# Sheet.net
KiCad netlist of a schematic drawn in Altium Designer
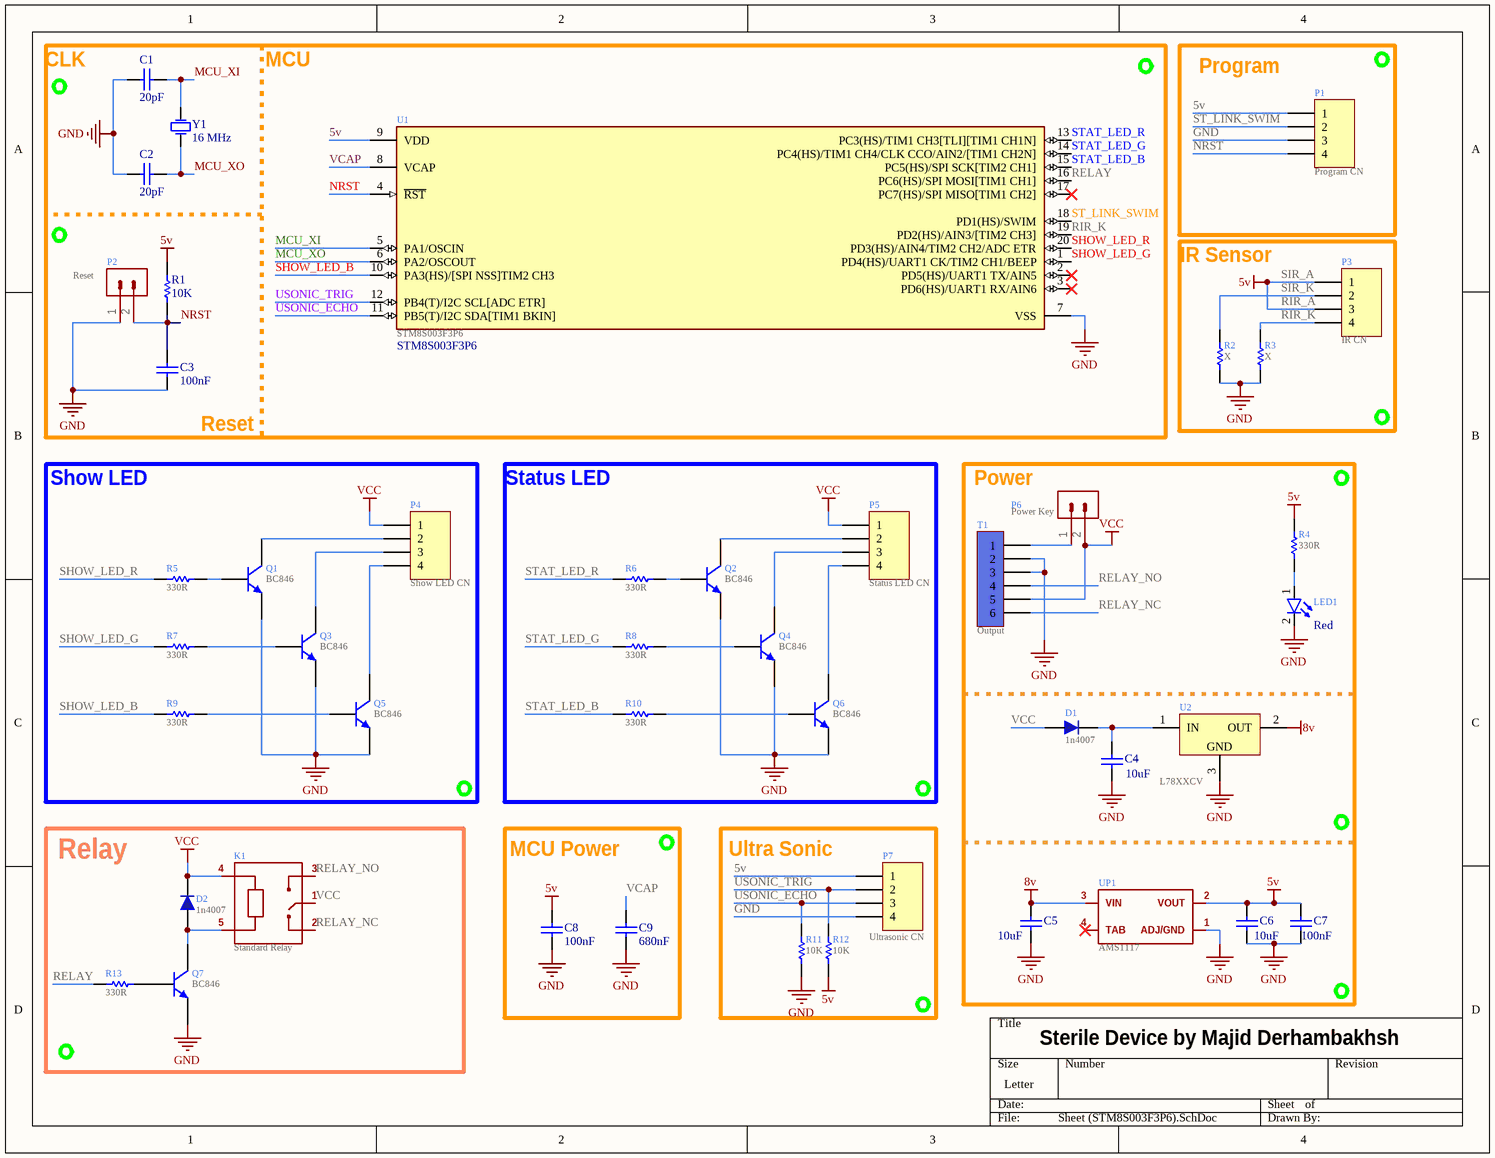
[diagram p0: Sheet (STM8S003F3P6).SchDoc]

(export (version "E")
  (design (tool "Eeschema 10.0.6"))
  (components
    (comp (ref "C1")
      (value "20pF")
      (footprint "CAP805")
      (description "TOTAL CAPACITOR SMD PACK")
      (fields (field (name "DESIGNER") "Majid Derhambakhsh"))
      (libsource (lib "Altium") (part "CAP SMD PACKAGE"))
    )
    (comp (ref "C2")
      (value "20pF")
      (footprint "CAP805")
      (description "TOTAL CAPACITOR SMD PACK")
      (fields (field (name "DESIGNER") "Majid Derhambakhsh"))
      (libsource (lib "Altium") (part "CAP SMD PACKAGE"))
    )
    (comp (ref "C3")
      (value "100nF")
      (footprint "Cap1206_(3216X15L)")
      (description "TOTAL CAPACITOR SMD PACK")
      (fields (field (name "DESIGNER") "Majid Derhambakhsh"))
      (libsource (lib "Altium") (part "CAP SMD PACKAGE"))
    )
    (comp (ref "C4")
      (value "10uF")
      (footprint "Cap1206_(3216X15)")
      (description "TOTAL CAPACITOR SMD PACK")
      (fields (field (name "DESIGNER") "Abbas Basereh"))
      (libsource (lib "Altium") (part "CAP SMD PACKAGE"))
    )
    (comp (ref "C5")
      (value "10uF")
      (footprint "Cap1206_(3216X15)")
      (description "TOTAL CAPACITOR SMD PACK")
      (fields (field (name "DESIGNER") "Abbas Basereh"))
      (libsource (lib "Altium") (part "CAP SMD PACKAGE"))
    )
    (comp (ref "C6")
      (value "10uF")
      (footprint "Cap1206_(3216X15)")
      (description "TOTAL CAPACITOR SMD PACK")
      (fields (field (name "DESIGNER") "Abbas Basereh"))
      (libsource (lib "Altium") (part "CAP SMD PACKAGE"))
    )
    (comp (ref "C7")
      (value "100nF")
      (footprint "Cap1206_(3216X15)")
      (description "TOTAL CAPACITOR SMD PACK")
      (fields (field (name "DESIGNER") "Majid Derhambakhsh"))
      (libsource (lib "Altium") (part "CAP SMD PACKAGE"))
    )
    (comp (ref "C8")
      (value "100nF")
      (footprint "Cap1206_(3216X15L)")
      (description "TOTAL CAPACITOR SMD PACK")
      (fields (field (name "DESIGNER") "Majid Derhambakhsh"))
      (libsource (lib "Altium") (part "CAP SMD PACKAGE"))
    )
    (comp (ref "C9")
      (value "680nF")
      (footprint "Cap1206_(3216X15L)")
      (description "TOTAL CAPACITOR SMD PACK")
      (fields (field (name "DESIGNER") "Majid Derhambakhsh"))
      (libsource (lib "Altium") (part "CAP SMD PACKAGE"))
    )
    (comp (ref "D1")
      (value "1n4007")
      (footprint "DIOM4629X24N")
      (description "Standard Rectifiers")
      (fields (field (name "MANUFACTURER") "DC COMPONENTS") (field (name "DESIGNER") "Abbas Basereh"))
      (libsource (lib "Altium") (part "1n4007 SMD M7"))
    )
    (comp (ref "D2")
      (value "1n4007")
      (footprint "DIOM4629X24N")
      (description "Standard Rectifiers")
      (fields (field (name "MANUFACTURER") "DC COMPONENTS") (field (name "DESIGNER") "Abbas Basereh"))
      (libsource (lib "Altium") (part "1n4007 SMD M7"))
    )
    (comp (ref "K1")
      (value "Standard Relay")
      (footprint "Milon Relay (18.85x15.35x15.70)")
      (description "Relay SPDT POWER NEEDLE")
      (fields (field (name "DESIGNER") "Ali Hafizi"))
      (libsource (lib "Altium library") (part "Relay"))
    )
    (comp (ref "LED1")
      (value "Red")
      (footprint "LED SMD 1206")
      (fields (field (name "COLOR") "Red") (field (name "DESIGNER") "Saeid Jorablo"))
      (libsource (lib "My Library") (part "LED"))
    )
    (comp (ref "P1")
      (value "Program CN")
      (footprint "HDR1X4")
      (description "Header, 4-Pin")
      (fields (field (name "PUBLISHER") "Altium Limited"))
      (libsource (lib "Miscellaneous Connectors") (part "Header 4"))
    )
    (comp (ref "P2")
      (value "Reset")
      (footprint "HDR 1X2 DIP TOP")
      (description "Header, 2-Pin")
      (fields (field (name "PUBLISHER") "Altium Limited"))
      (libsource (lib "Altium library") (part "Header 2"))
    )
    (comp (ref "P3")
      (value "IR CN")
      (footprint "HDR1X4")
      (description "Header, 4-Pin")
      (fields (field (name "PUBLISHER") "Altium Limited"))
      (libsource (lib "Miscellaneous Connectors") (part "Header 4"))
    )
    (comp (ref "P4")
      (value "Show LED CN")
      (footprint "HDR1X4")
      (description "Header, 4-Pin")
      (fields (field (name "PUBLISHER") "Altium Limited"))
      (libsource (lib "Miscellaneous Connectors") (part "Header 4"))
    )
    (comp (ref "P5")
      (value "Status LED CN")
      (footprint "HDR1X4")
      (description "Header, 4-Pin")
      (fields (field (name "PUBLISHER") "Altium Limited"))
      (libsource (lib "Miscellaneous Connectors") (part "Header 4"))
    )
    (comp (ref "P6")
      (value "Power Key")
      (footprint "HDR 1X2 DIP TOP")
      (description "Header, 2-Pin")
      (fields (field (name "PUBLISHER") "Altium Limited"))
      (libsource (lib "Altium library") (part "Header 2"))
    )
    (comp (ref "P7")
      (value "Ultrasonic CN")
      (footprint "HDR1X4")
      (description "Header, 4-Pin")
      (fields (field (name "PUBLISHER") "Altium Limited"))
      (libsource (lib "Miscellaneous Connectors") (part "Header 4"))
    )
    (comp (ref "Q1")
      (value "BC846")
      (footprint "SOT23_L")
      (description "NPN General-purpose Transistor")
      (fields (field (name "PUBLISHER") "Abbas Basereh"))
      (libsource (lib "Altium") (part "BC846"))
    )
    (comp (ref "Q2")
      (value "BC846")
      (footprint "SOT23_L")
      (description "NPN General-purpose Transistor")
      (fields (field (name "PUBLISHER") "Abbas Basereh"))
      (libsource (lib "Altium") (part "BC846"))
    )
    (comp (ref "Q3")
      (value "BC846")
      (footprint "SOT23_L")
      (description "NPN General-purpose Transistor")
      (fields (field (name "PUBLISHER") "Abbas Basereh"))
      (libsource (lib "Altium") (part "BC846"))
    )
    (comp (ref "Q4")
      (value "BC846")
      (footprint "SOT23_L")
      (description "NPN General-purpose Transistor")
      (fields (field (name "PUBLISHER") "Abbas Basereh"))
      (libsource (lib "Altium") (part "BC846"))
    )
    (comp (ref "Q5")
      (value "BC846")
      (footprint "SOT23_L")
      (description "NPN General-purpose Transistor")
      (fields (field (name "PUBLISHER") "Abbas Basereh"))
      (libsource (lib "Altium") (part "BC846"))
    )
    (comp (ref "Q6")
      (value "BC846")
      (footprint "SOT23_L")
      (description "NPN General-purpose Transistor")
      (fields (field (name "PUBLISHER") "Abbas Basereh"))
      (libsource (lib "Altium") (part "BC846"))
    )
    (comp (ref "Q7")
      (value "BC846")
      (footprint "SOT23_L")
      (description "NPN General-purpose Transistor")
      (fields (field (name "PUBLISHER") "Abbas Basereh"))
      (libsource (lib "Altium") (part "BC846"))
    )
    (comp (ref "R1")
      (value "10K")
      (footprint "RES1206 _(3216X08L)")
      (description "TOTAL SMD RESISTOR PACK")
      (fields (field (name "DESIGNER") "Abbas Basereh"))
      (libsource (lib "Altium") (part "RES SMD PACKAGE"))
    )
    (comp (ref "R2")
      (value "X")
      (footprint "RES1206 _(3216X08L)")
      (description "TOTAL SMD RESISTOR PACK")
      (fields (field (name "DESIGNER") "Abbas Basereh"))
      (libsource (lib "Altium") (part "RES SMD PACKAGE"))
    )
    (comp (ref "R3")
      (value "X")
      (footprint "RES1206 _(3216X08L)")
      (description "TOTAL SMD RESISTOR PACK")
      (fields (field (name "DESIGNER") "Abbas Basereh"))
      (libsource (lib "Altium") (part "RES SMD PACKAGE"))
    )
    (comp (ref "R4")
      (value "330R")
      (footprint "RES1206 _(3216X08L)")
      (description "TOTAL SMD RESISTOR PACK")
      (fields (field (name "DESIGNER") "Abbas Basereh"))
      (libsource (lib "Altium") (part "RES SMD PACKAGE"))
    )
    (comp (ref "R5")
      (value "330R")
      (footprint "RES1206 _(3216X08L)")
      (description "TOTAL SMD RESISTOR PACK")
      (fields (field (name "DESIGNER") "Abbas Basereh"))
      (libsource (lib "Altium") (part "RES SMD PACKAGE"))
    )
    (comp (ref "R6")
      (value "330R")
      (footprint "RES1206 _(3216X08L)")
      (description "TOTAL SMD RESISTOR PACK")
      (fields (field (name "DESIGNER") "Abbas Basereh"))
      (libsource (lib "Altium") (part "RES SMD PACKAGE"))
    )
    (comp (ref "R7")
      (value "330R")
      (footprint "RES1206 _(3216X08L)")
      (description "TOTAL SMD RESISTOR PACK")
      (fields (field (name "DESIGNER") "Abbas Basereh"))
      (libsource (lib "Altium") (part "RES SMD PACKAGE"))
    )
    (comp (ref "R8")
      (value "330R")
      (footprint "RES1206 _(3216X08L)")
      (description "TOTAL SMD RESISTOR PACK")
      (fields (field (name "DESIGNER") "Abbas Basereh"))
      (libsource (lib "Altium") (part "RES SMD PACKAGE"))
    )
    (comp (ref "R9")
      (value "330R")
      (footprint "RES1206 _(3216X08L)")
      (description "TOTAL SMD RESISTOR PACK")
      (fields (field (name "DESIGNER") "Abbas Basereh"))
      (libsource (lib "Altium") (part "RES SMD PACKAGE"))
    )
    (comp (ref "R10")
      (value "330R")
      (footprint "RES1206 _(3216X08L)")
      (description "TOTAL SMD RESISTOR PACK")
      (fields (field (name "DESIGNER") "Abbas Basereh"))
      (libsource (lib "Altium") (part "RES SMD PACKAGE"))
    )
    (comp (ref "R11")
      (value "10K")
      (footprint "RES1206 _(3216X08L)")
      (description "TOTAL SMD RESISTOR PACK")
      (fields (field (name "DESIGNER") "Abbas Basereh"))
      (libsource (lib "Altium") (part "RES SMD PACKAGE"))
    )
    (comp (ref "R12")
      (value "10K")
      (footprint "RES1206 _(3216X08L)")
      (description "TOTAL SMD RESISTOR PACK")
      (fields (field (name "DESIGNER") "Abbas Basereh"))
      (libsource (lib "Altium") (part "RES SMD PACKAGE"))
    )
    (comp (ref "R13")
      (value "330R")
      (footprint "RES1206 _(3216X08L)")
      (description "TOTAL SMD RESISTOR PACK")
      (fields (field (name "DESIGNER") "Abbas Basereh"))
      (libsource (lib "Altium") (part "RES SMD PACKAGE"))
    )
    (comp (ref "T1")
      (value "Output")
      (footprint "KF301-6PIN")
      (description "Terminal 6 Pin 250VAC 16A")
      (libsource (lib "Altium") (part "KF301-6Pin_Terminal"))
    )
    (comp (ref "U1")
      (value "STM8S003F3P6")
      (footprint "STMicroelectronics_STM8S003F3P6_0")
      (description "IC STM8 STM8S Microcontroller IC 8-Bit 16MHz 8KB (8K x 8) FLASH 20-TSSOP")
      (fields
        (field (name "VOLTAGE") "2.95V~5.5V")
        (field (name "MANUFACTURER") "STMicroelectronics")
        (field (name "PART NUMBER") "STM8S003F3P6")
      )
      (libsource (lib "Altium library") (part "STM8S003F3P6"))
    )
    (comp (ref "U2")
      (value "L78XXCV")
      (footprint "78XXCV - Right")
      (description "Fixed Voltage Regulator")
      (fields (field (name "DESIGNER") "Saeid Jorablo"))
      (libsource (lib "My Library") (part "L78XXCV"))
    )
    (comp (ref "UP1")
      (value "AMS1117")
      (footprint "SOT223")
      (description "x.x Volt, 800mA Low-Dropout Linear Regulator, 4-pin SOT-223")
      (fields (field (name "DESIGNER") "Ali Hafizi"))
      (libsource (lib "Altium library") (part "AMS1117"))
    )
    (comp (ref "Y1")
      (value "16 MHz")
      (footprint "XTAL 16MHZ")
      (description "XTAL Crystal")
      (fields (field (name "DESIGNER") "ABBAS BASEREH"))
      (libsource (lib "Altium") (part "XTAL"))
    )
  )
  (nets
    (net (code "1") (name "/MCU_XI") (class "Default")
      (node (ref "C1") (pin "1") (pinfunction "1_1") (pintype "passive"))
      (node (ref "U1") (pin "5") (pinfunction "PA1/OSCIN_5") (pintype "bidirectional"))
      (node (ref "Y1") (pin "2") (pinfunction "OSC2_2") (pintype "passive"))
    )
    (net (code "2") (name "/MCU_XO") (class "Default")
      (node (ref "C2") (pin "1") (pinfunction "1_1") (pintype "passive"))
      (node (ref "U1") (pin "6") (pinfunction "PA2/OSCOUT_6") (pintype "bidirectional"))
      (node (ref "Y1") (pin "1") (pinfunction "OSC1_1") (pintype "passive"))
    )
    (net (code "3") (name "/NRST") (class "Default")
      (node (ref "C3") (pin "2") (pinfunction "2_2") (pintype "passive"))
      (node (ref "P1") (pin "4") (pinfunction "4_4") (pintype "passive"))
      (node (ref "P2") (pin "2") (pinfunction "2_2") (pintype "passive"))
      (node (ref "R1") (pin "1") (pinfunction "1_1") (pintype "passive"))
      (node (ref "U1") (pin "4") (pinfunction "~{RST}_4") (pintype "input"))
    )
    (net (code "4") (name "/RELAY") (class "Default")
      (node (ref "R13") (pin "1") (pinfunction "1_1") (pintype "passive"))
      (node (ref "U1") (pin "16") (pinfunction "PC6(HS)/SPI_MOSI[TIM1_CH1]_16") (pintype "bidirectional"))
    )
    (net (code "5") (name "/RELAY_NC") (class "Default")
      (node (ref "K1") (pin "2") (pinfunction "N.C_2") (pintype "open_collector"))
      (node (ref "T1") (pin "6") (pinfunction "6_6") (pintype "passive"))
    )
    (net (code "6") (name "/RELAY_NO") (class "Default")
      (node (ref "K1") (pin "3") (pinfunction "N.O_3") (pintype "open_collector"))
      (node (ref "T1") (pin "4") (pinfunction "4_4") (pintype "passive"))
    )
    (net (code "7") (name "/RIR_K") (class "Default")
      (node (ref "P3") (pin "4") (pinfunction "4_4") (pintype "passive"))
      (node (ref "R3") (pin "1") (pinfunction "1_1") (pintype "passive"))
      (node (ref "U1") (pin "19") (pinfunction "PD2(HS)/AIN3/[TIM2_CH3]_19") (pintype "bidirectional"))
    )
    (net (code "8") (name "/SHOW_LED_B") (class "Default")
      (node (ref "R9") (pin "1") (pinfunction "1_1") (pintype "passive"))
      (node (ref "U1") (pin "10") (pinfunction "PA3(HS)/[SPI_NSS]TIM2_CH3_10") (pintype "bidirectional"))
    )
    (net (code "9") (name "/SHOW_LED_G") (class "Default")
      (node (ref "R7") (pin "1") (pinfunction "1_1") (pintype "passive"))
      (node (ref "U1") (pin "1") (pinfunction "PD4(HS)/UART1_CK/TIM2_CH1/BEEP_1") (pintype "bidirectional"))
    )
    (net (code "10") (name "/SHOW_LED_R") (class "Default")
      (node (ref "R5") (pin "1") (pinfunction "1_1") (pintype "passive"))
      (node (ref "U1") (pin "20") (pinfunction "PD3(HS)/AIN4/TIM2_CH2/ADC_ETR_20") (pintype "bidirectional"))
    )
    (net (code "11") (name "/SIR_K") (class "Default")
      (node (ref "P3") (pin "2") (pinfunction "2_2") (pintype "passive"))
      (node (ref "R2") (pin "1") (pinfunction "1_1") (pintype "passive"))
    )
    (net (code "12") (name "/STAT_LED_B") (class "Default")
      (node (ref "R10") (pin "1") (pinfunction "1_1") (pintype "passive"))
      (node (ref "U1") (pin "15") (pinfunction "PC5(HS)/SPI_SCK[TIM2_CH1]_15") (pintype "bidirectional"))
    )
    (net (code "13") (name "/STAT_LED_G") (class "Default")
      (node (ref "R8") (pin "1") (pinfunction "1_1") (pintype "passive"))
      (node (ref "U1") (pin "14") (pinfunction "PC4(HS)/TIM1_CH4/CLK_CCO/AIN2/[TIM1_CH2N]_14") (pintype "bidirectional"))
    )
    (net (code "14") (name "/STAT_LED_R") (class "Default")
      (node (ref "R6") (pin "1") (pinfunction "1_1") (pintype "passive"))
      (node (ref "U1") (pin "13") (pinfunction "PC3(HS)/TIM1_CH3[TLI][TIM1_CH1N]_13") (pintype "bidirectional"))
    )
    (net (code "15") (name "/ST_LINK_SWIM") (class "Default")
      (node (ref "P1") (pin "2") (pinfunction "2_2") (pintype "passive"))
      (node (ref "U1") (pin "18") (pinfunction "PD1(HS)/SWIM_18") (pintype "bidirectional"))
    )
    (net (code "16") (name "/USONIC_ECHO") (class "Default")
      (node (ref "P7") (pin "3") (pinfunction "3_3") (pintype "passive"))
      (node (ref "R11") (pin "2") (pinfunction "2_2") (pintype "passive"))
      (node (ref "U1") (pin "11") (pinfunction "PB5(T)/I2C_SDA[TIM1_BKIN]_11") (pintype "bidirectional"))
    )
    (net (code "17") (name "/USONIC_TRIG") (class "Default")
      (node (ref "P7") (pin "2") (pinfunction "2_2") (pintype "passive"))
      (node (ref "R12") (pin "2") (pinfunction "2_2") (pintype "passive"))
      (node (ref "U1") (pin "12") (pinfunction "PB4(T)/I2C_SCL[ADC_ETR]_12") (pintype "bidirectional"))
    )
    (net (code "18") (name "/VCAP") (class "Default")
      (node (ref "C9") (pin "2") (pinfunction "2_2") (pintype "passive"))
      (node (ref "U1") (pin "8") (pinfunction "VCAP_8") (pintype "power_in"))
    )
    (net (code "19") (name "5v") (class "Default")
      (node (ref "C6") (pin "2") (pinfunction "2_2") (pintype "passive"))
      (node (ref "C7") (pin "2") (pinfunction "2_2") (pintype "passive"))
      (node (ref "C8") (pin "2") (pinfunction "2_2") (pintype "passive"))
      (node (ref "P1") (pin "1") (pinfunction "1_1") (pintype "passive"))
      (node (ref "P3") (pin "1") (pinfunction "1_1") (pintype "passive"))
      (node (ref "P3") (pin "3") (pinfunction "3_3") (pintype "passive"))
      (node (ref "P7") (pin "1") (pinfunction "1_1") (pintype "passive"))
      (node (ref "R1") (pin "2") (pinfunction "2_2") (pintype "passive"))
      (node (ref "R12") (pin "1") (pinfunction "1_1") (pintype "passive"))
      (node (ref "R4") (pin "2") (pinfunction "2_2") (pintype "passive"))
      (node (ref "U1") (pin "9") (pinfunction "VDD_9") (pintype "power_in"))
      (node (ref "UP1") (pin "2") (pinfunction "VOUT_2") (pintype "open_collector"))
    )
    (net (code "20") (name "8v") (class "Default")
      (node (ref "C5") (pin "2") (pinfunction "2_2") (pintype "passive"))
      (node (ref "U2") (pin "2") (pinfunction "OUT_2") (pintype "passive"))
      (node (ref "UP1") (pin "3") (pinfunction "VIN_3") (pintype "open_collector"))
    )
    (net (code "21") (name "GND") (class "Default")
      (node (ref "C1") (pin "2") (pinfunction "2_2") (pintype "passive"))
      (node (ref "C2") (pin "2") (pinfunction "2_2") (pintype "passive"))
      (node (ref "C3") (pin "1") (pinfunction "1_1") (pintype "passive"))
      (node (ref "C4") (pin "1") (pinfunction "1_1") (pintype "passive"))
      (node (ref "C5") (pin "1") (pinfunction "1_1") (pintype "passive"))
      (node (ref "C6") (pin "1") (pinfunction "1_1") (pintype "passive"))
      (node (ref "C7") (pin "1") (pinfunction "1_1") (pintype "passive"))
      (node (ref "C8") (pin "1") (pinfunction "1_1") (pintype "passive"))
      (node (ref "C9") (pin "1") (pinfunction "1_1") (pintype "passive"))
      (node (ref "LED1") (pin "2") (pinfunction "K_2") (pintype "passive"))
      (node (ref "P1") (pin "3") (pinfunction "3_3") (pintype "passive"))
      (node (ref "P2") (pin "1") (pinfunction "1_1") (pintype "passive"))
      (node (ref "P7") (pin "4") (pinfunction "4_4") (pintype "passive"))
      (node (ref "Q1") (pin "2") (pinfunction "E_2") (pintype "passive"))
      (node (ref "Q2") (pin "2") (pinfunction "E_2") (pintype "passive"))
      (node (ref "Q3") (pin "2") (pinfunction "E_2") (pintype "passive"))
      (node (ref "Q4") (pin "2") (pinfunction "E_2") (pintype "passive"))
      (node (ref "Q5") (pin "2") (pinfunction "E_2") (pintype "passive"))
      (node (ref "Q6") (pin "2") (pinfunction "E_2") (pintype "passive"))
      (node (ref "Q7") (pin "2") (pinfunction "E_2") (pintype "passive"))
      (node (ref "R11") (pin "1") (pinfunction "1_1") (pintype "passive"))
      (node (ref "R2") (pin "2") (pinfunction "2_2") (pintype "passive"))
      (node (ref "R3") (pin "2") (pinfunction "2_2") (pintype "passive"))
      (node (ref "T1") (pin "2") (pinfunction "2_2") (pintype "passive"))
      (node (ref "T1") (pin "3") (pinfunction "3_3") (pintype "passive"))
      (node (ref "U1") (pin "7") (pinfunction "VSS_7") (pintype "power_in"))
      (node (ref "U2") (pin "3") (pinfunction "GND_3") (pintype "passive"))
      (node (ref "UP1") (pin "1") (pinfunction "ADJ/GND_1") (pintype "open_collector"))
    )
    (net (code "22") (name "Net-(LED1-A)") (class "Default")
      (node (ref "LED1") (pin "1") (pinfunction "A_1") (pintype "passive"))
      (node (ref "R4") (pin "1") (pinfunction "1_1") (pintype "passive"))
    )
    (net (code "23") (name "Net-(P6-Pad1)") (class "Default")
      (node (ref "P6") (pin "1") (pinfunction "1_1") (pintype "passive"))
      (node (ref "T1") (pin "1") (pinfunction "1_1") (pintype "passive"))
    )
    (net (code "24") (name "Net-(Q1-B)") (class "Default")
      (node (ref "Q1") (pin "1") (pinfunction "B_1") (pintype "passive"))
      (node (ref "R5") (pin "2") (pinfunction "2_2") (pintype "passive"))
    )
    (net (code "25") (name "Net-(Q1-C)") (class "Default")
      (node (ref "P4") (pin "2") (pinfunction "2_2") (pintype "passive"))
      (node (ref "Q1") (pin "3") (pinfunction "C_3") (pintype "passive"))
    )
    (net (code "26") (name "Net-(Q2-B)") (class "Default")
      (node (ref "Q2") (pin "1") (pinfunction "B_1") (pintype "passive"))
      (node (ref "R6") (pin "2") (pinfunction "2_2") (pintype "passive"))
    )
    (net (code "27") (name "Net-(Q2-C)") (class "Default")
      (node (ref "P5") (pin "2") (pinfunction "2_2") (pintype "passive"))
      (node (ref "Q2") (pin "3") (pinfunction "C_3") (pintype "passive"))
    )
    (net (code "28") (name "Net-(Q3-B)") (class "Default")
      (node (ref "Q3") (pin "1") (pinfunction "B_1") (pintype "passive"))
      (node (ref "R7") (pin "2") (pinfunction "2_2") (pintype "passive"))
    )
    (net (code "29") (name "Net-(Q3-C)") (class "Default")
      (node (ref "P4") (pin "3") (pinfunction "3_3") (pintype "passive"))
      (node (ref "Q3") (pin "3") (pinfunction "C_3") (pintype "passive"))
    )
    (net (code "30") (name "Net-(Q4-B)") (class "Default")
      (node (ref "Q4") (pin "1") (pinfunction "B_1") (pintype "passive"))
      (node (ref "R8") (pin "2") (pinfunction "2_2") (pintype "passive"))
    )
    (net (code "31") (name "Net-(Q4-C)") (class "Default")
      (node (ref "P5") (pin "3") (pinfunction "3_3") (pintype "passive"))
      (node (ref "Q4") (pin "3") (pinfunction "C_3") (pintype "passive"))
    )
    (net (code "32") (name "Net-(Q5-B)") (class "Default")
      (node (ref "Q5") (pin "1") (pinfunction "B_1") (pintype "passive"))
      (node (ref "R9") (pin "2") (pinfunction "2_2") (pintype "passive"))
    )
    (net (code "33") (name "Net-(Q5-C)") (class "Default")
      (node (ref "P4") (pin "4") (pinfunction "4_4") (pintype "passive"))
      (node (ref "Q5") (pin "3") (pinfunction "C_3") (pintype "passive"))
    )
    (net (code "34") (name "Net-(Q6-B)") (class "Default")
      (node (ref "Q6") (pin "1") (pinfunction "B_1") (pintype "passive"))
      (node (ref "R10") (pin "2") (pinfunction "2_2") (pintype "passive"))
    )
    (net (code "35") (name "Net-(Q6-C)") (class "Default")
      (node (ref "P5") (pin "4") (pinfunction "4_4") (pintype "passive"))
      (node (ref "Q6") (pin "3") (pinfunction "C_3") (pintype "passive"))
    )
    (net (code "36") (name "Net-(Q7-B)") (class "Default")
      (node (ref "Q7") (pin "1") (pinfunction "B_1") (pintype "passive"))
      (node (ref "R13") (pin "2") (pinfunction "2_2") (pintype "passive"))
    )
    (net (code "37") (name "Net-(Q7-C)") (class "Default")
      (node (ref "D2") (pin "1") (pintype "passive"))
      (node (ref "K1") (pin "5") (pinfunction "A_5") (pintype "open_collector"))
      (node (ref "Q7") (pin "3") (pinfunction "C_3") (pintype "passive"))
    )
    (net (code "38") (name "Net-(U2-IN)") (class "Default")
      (node (ref "C4") (pin "2") (pinfunction "2_2") (pintype "passive"))
      (node (ref "D1") (pin "2") (pintype "passive"))
      (node (ref "U2") (pin "1") (pinfunction "IN_1") (pintype "passive"))
    )
    (net (code "39") (name "VCC") (class "Default")
      (node (ref "D1") (pin "1") (pintype "passive"))
      (node (ref "D2") (pin "2") (pintype "passive"))
      (node (ref "K1") (pin "1") (pinfunction "COM_1") (pintype "open_collector"))
      (node (ref "K1") (pin "4") (pinfunction "A_4") (pintype "open_collector"))
      (node (ref "P4") (pin "1") (pinfunction "1_1") (pintype "passive"))
      (node (ref "P5") (pin "1") (pinfunction "1_1") (pintype "passive"))
      (node (ref "P6") (pin "2") (pinfunction "2_2") (pintype "passive"))
      (node (ref "T1") (pin "5") (pinfunction "5_5") (pintype "passive"))
    )
    (net (code "40") (name "unconnected-(U1-PC7(HS){slash}SPI_MISO[TIM1_CH2]-Pad17)") (class "Default")
      (node (ref "U1") (pin "17") (pinfunction "PC7(HS)/SPI_MISO[TIM1_CH2]_17") (pintype "bidirectional+no_connect"))
    )
    (net (code "41") (name "unconnected-(U1-PD5(HS){slash}UART1_TX{slash}AIN5-Pad2)") (class "Default")
      (node (ref "U1") (pin "2") (pinfunction "PD5(HS)/UART1_TX/AIN5_2") (pintype "bidirectional+no_connect"))
    )
    (net (code "42") (name "unconnected-(U1-PD6(HS){slash}UART1_RX{slash}AIN6-Pad3)") (class "Default")
      (node (ref "U1") (pin "3") (pinfunction "PD6(HS)/UART1_RX/AIN6_3") (pintype "bidirectional+no_connect"))
    )
    (net (code "43") (name "unconnected-(UP1-TAB-Pad4)") (class "Default")
      (node (ref "UP1") (pin "4") (pinfunction "TAB_4") (pintype "open_collector+no_connect"))
    )
  )
)
